# USB.net
KiCad netlist of a schematic drawn in Altium Designer
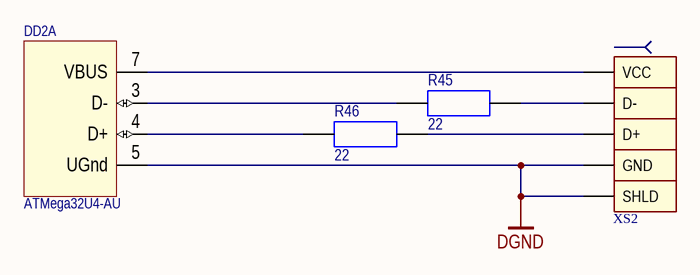
[diagram p0: USB.SchDoc]

(export (version "E")
  (design (tool "Eeschema 10.0.6"))
  (components
    (comp (ref "DD2")
      (value "ATMega32U4-AU")
      (footprint "Atmel Microcontroller 8-Bit Automotive AVR:44ML_L")
      (libsource (lib "Microcontrollers") (part "ATMega32U4"))
    )
    (comp (ref "R45")
      (value "22")
      (footprint "SMDRC0805")
      (description "Generic resistor")
      (fields (field (name "PARTNUMBER") "Resistor 0805 22"))
      (libsource (lib "library") (part "Resistor"))
    )
    (comp (ref "R46")
      (value "22")
      (footprint "SMDRC0805")
      (description "Generic resistor")
      (fields (field (name "PARTNUMBER") "Resistor 0805 22"))
      (libsource (lib "library") (part "Resistor"))
    )
    (comp (ref "XS2")
      (value "USB B A-09 РОЗЕТКА НА ПЛАТУ")
      (footprint "Connector:USB2.0B_Vertical")
      (description "USB-B Vertical")
      (libsource (lib "Connector") (part "USB2.0-BR"))
    )
  )
  (nets
    (net (code "1") (name "DGND") (class "Default")
      (node (ref "DD2") (pin "5") (pinfunction "UGnd_5") (pintype "power_in"))
      (node (ref "XS2") (pin "GND") (pinfunction "GND_GND") (pintype "passive"))
      (node (ref "XS2") (pin "SHLD") (pinfunction "SHLD_SHLD") (pintype "passive"))
    )
    (net (code "2") (name "Net-(DD2A-D+)") (class "Default")
      (node (ref "DD2") (pin "4") (pinfunction "D+_4") (pintype "bidirectional"))
      (node (ref "R46") (pin "1") (pinfunction "1_1") (pintype "passive"))
    )
    (net (code "3") (name "Net-(DD2A-D-)") (class "Default")
      (node (ref "DD2") (pin "3") (pinfunction "D-_3") (pintype "bidirectional"))
      (node (ref "R45") (pin "1") (pinfunction "1_1") (pintype "passive"))
    )
    (net (code "4") (name "Net-(DD2A-VBUS)") (class "Default")
      (node (ref "DD2") (pin "7") (pinfunction "VBUS_7") (pintype "passive"))
      (node (ref "XS2") (pin "VCC") (pinfunction "VCC_VCC") (pintype "passive"))
    )
    (net (code "5") (name "Net-(R45-Pad2)") (class "Default")
      (node (ref "R45") (pin "2") (pinfunction "2_2") (pintype "passive"))
      (node (ref "XS2") (pin "D-") (pinfunction "D-_D-") (pintype "passive"))
    )
    (net (code "6") (name "Net-(R46-Pad2)") (class "Default")
      (node (ref "R46") (pin "2") (pinfunction "2_2") (pintype "passive"))
      (node (ref "XS2") (pin "D+") (pinfunction "D+_D+") (pintype "passive"))
    )
  )
)
